# LCDClock.net
KiCad netlist of a schematic drawn in EAGLE
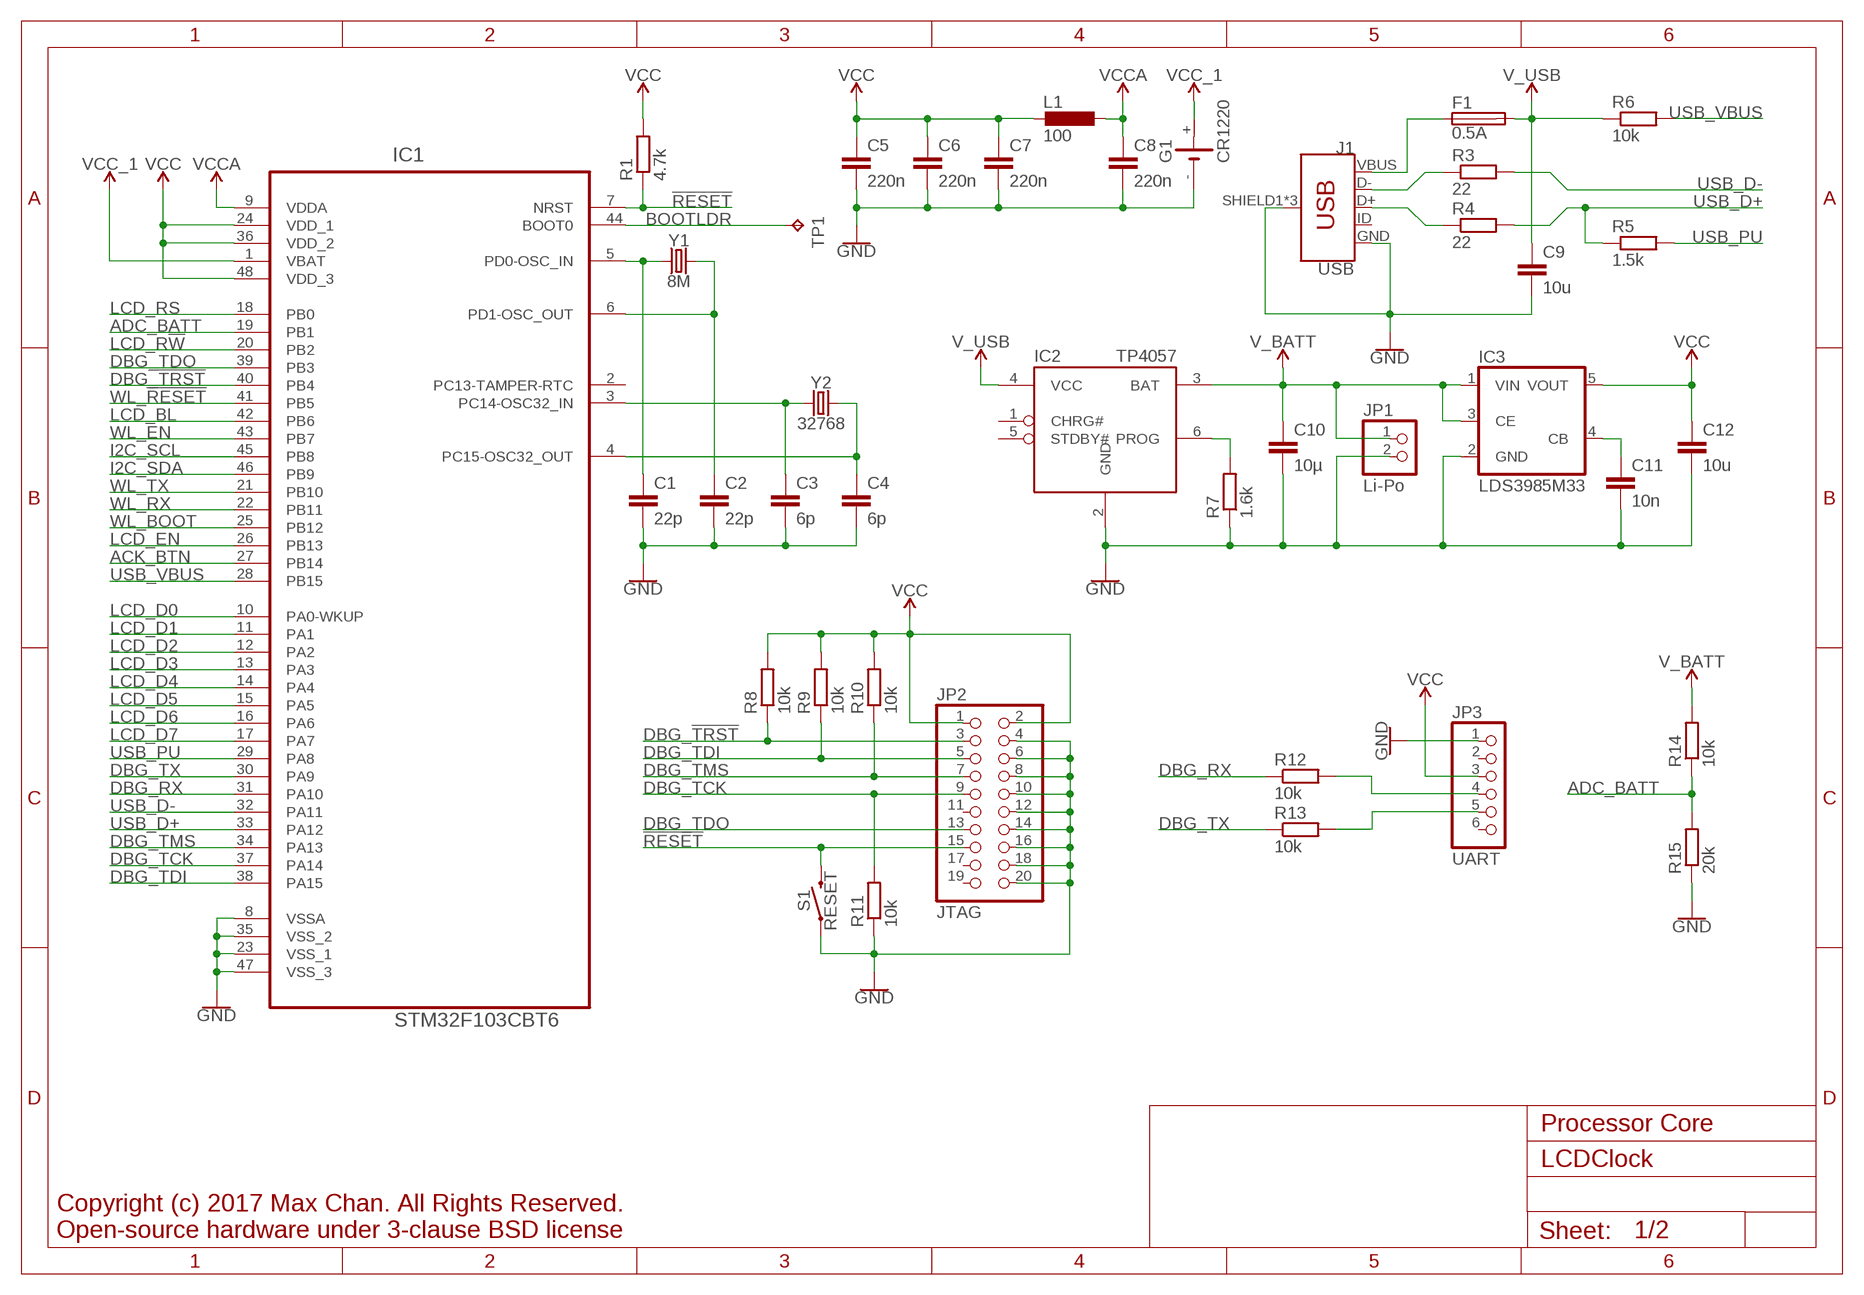
[diagram p0: schematic, sheet 1]
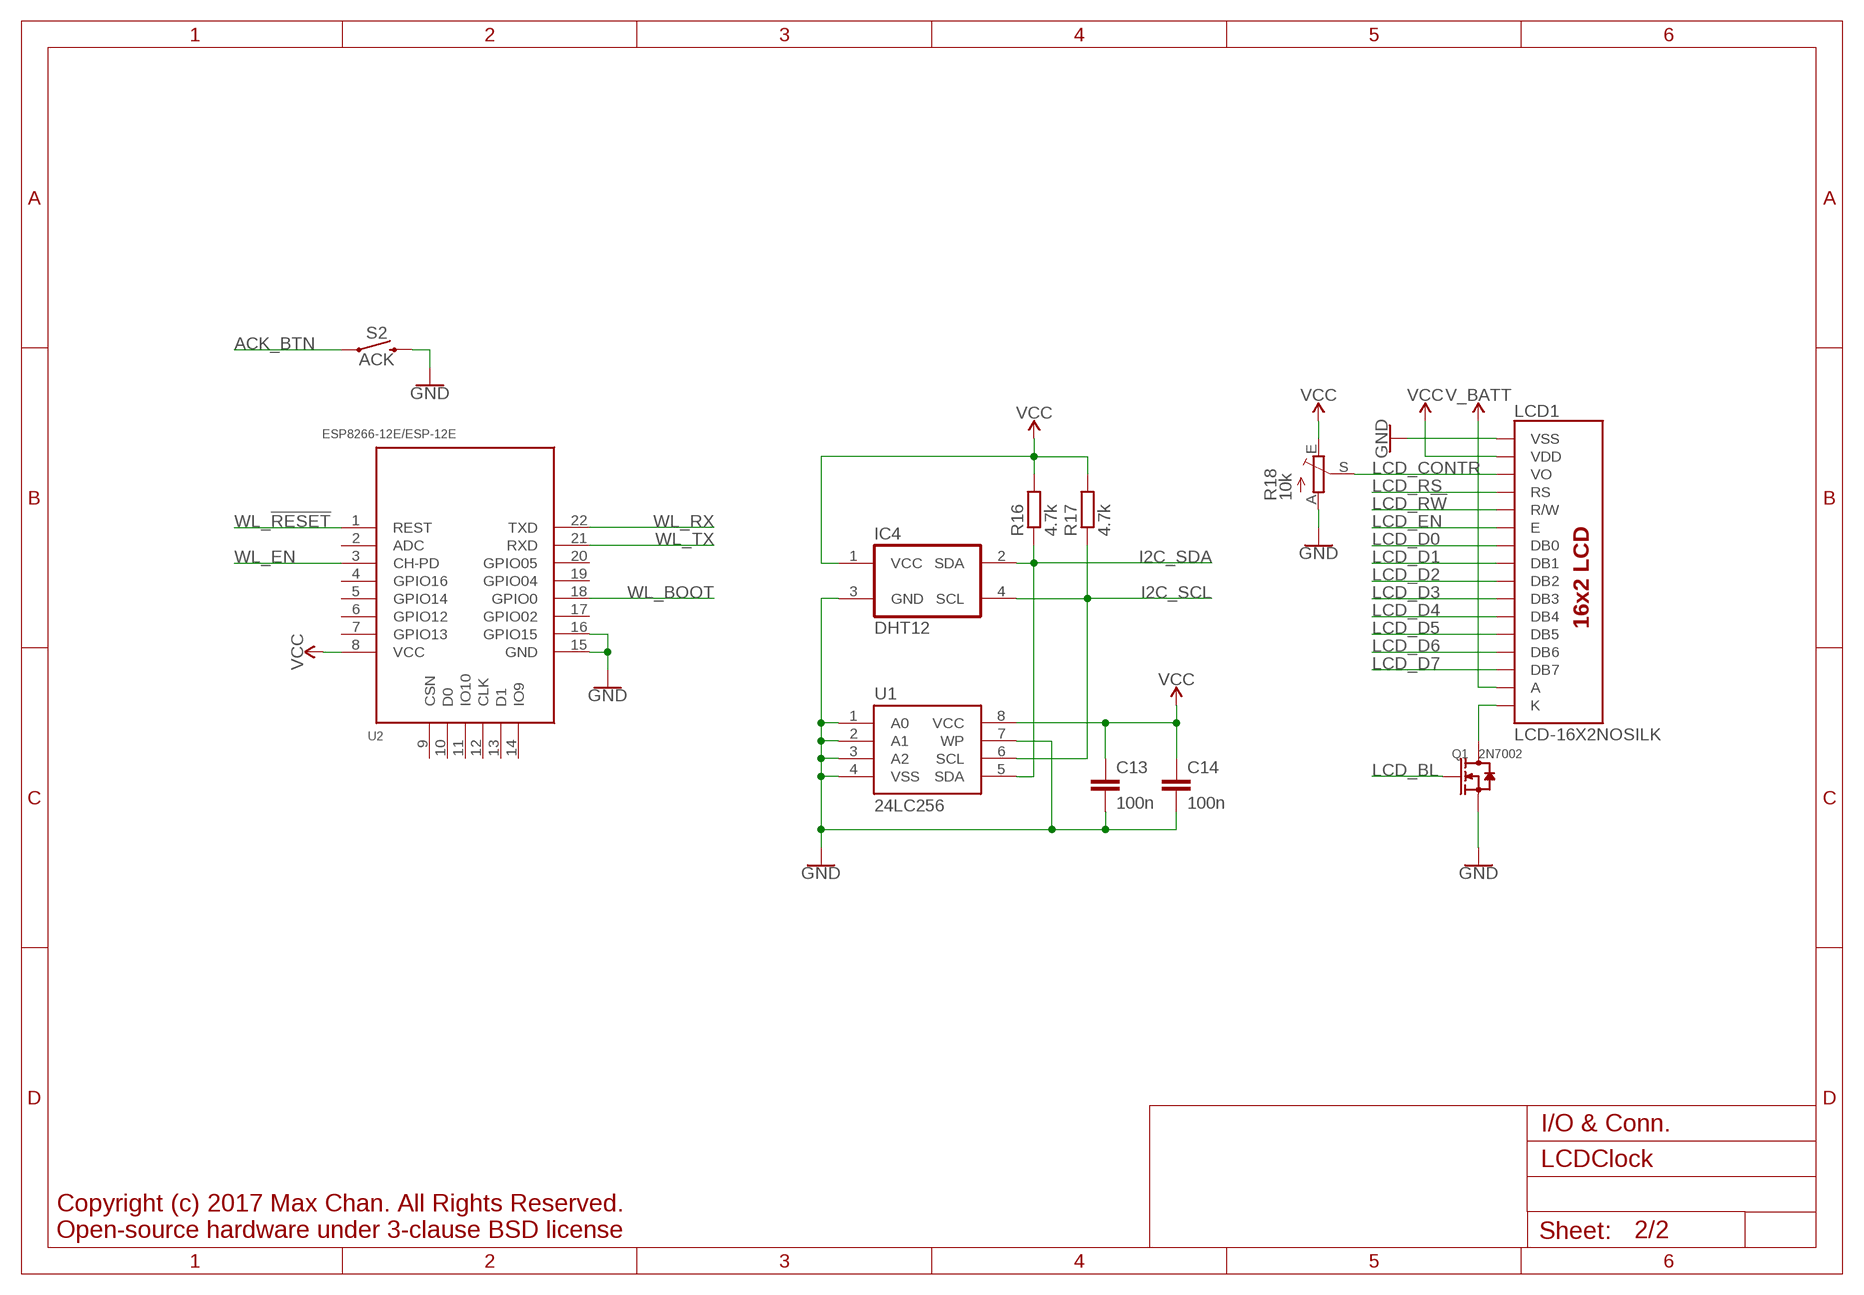
[diagram p1: schematic, sheet 2]

(export (version "E")
  (design (tool "Eeschema 10.0.6"))
  (components
    (comp (ref "C13")
      (value "100n")
      (footprint "eagle-import:C0603")
      (libsource (lib "eagle-import") (part "C-EUC0603"))
    )
    (comp (ref "C14")
      (value "100n")
      (footprint "eagle-import:C0603")
      (libsource (lib "eagle-import") (part "C-EUC0603"))
    )
    (comp (ref "IC4")
      (value "DHT12")
      (footprint "eagle-import:DHT12")
      (libsource (lib "eagle-import") (part "DHT12"))
    )
    (comp (ref "LCD1")
      (value "LCD-16X2NOSILK")
      (footprint "eagle-import:LCD-16X2_NOSILK")
      (libsource (lib "eagle-import") (part "LCD-16X2NOSILK"))
    )
    (comp (ref "Q1")
      (value "2N7002")
      (footprint "eagle-import:SOT-23")
      (fields (field (name "MPN") "2N7002,215"))
      (libsource (lib "eagle-import") (part "SMD-MOSFET-N-CH-60V-300MA-LOGIC-LEVEL-FET-2N7002(SOT-23)"))
    )
    (comp (ref "R16")
      (value "4.7k")
      (footprint "eagle-import:R0603")
      (libsource (lib "eagle-import") (part "R-EU_R0603"))
    )
    (comp (ref "R17")
      (value "4.7k")
      (footprint "eagle-import:R0603")
      (libsource (lib "eagle-import") (part "R-EU_R0603"))
    )
    (comp (ref "R18")
      (value "10k")
      (footprint "eagle-import:CA6V")
      (libsource (lib "eagle-import") (part "TRIM_EU-CA6V"))
    )
    (comp (ref "S2")
      (value "ACK")
      (footprint "eagle-import:TACTILE_SWITCH_PTH_RIGHT_ANGLE_KIT")
      (libsource (lib "eagle-import") (part "MOMENTARY-SWITCH-SPST-PTH-RIGHT-ANGLE-KIT"))
    )
    (comp (ref "U1")
      (value "24LC256")
      (footprint "eagle-import:SO08")
      (libsource (lib "eagle-import") (part "EEPROM-I2CSMD"))
    )
    (comp (ref "U2")
      (value "ESP8266-12E/ESP-12E")
      (footprint "eagle-import:LGA22-2.0-24X16MM")
      (libsource (lib "eagle-import") (part "MOUDLE-WIFI-ESP8266-12E/ESP-12E(22P-24X16MM)"))
    )
    (comp (ref "C1")
      (value "22p")
      (footprint "eagle-import:C0603")
      (libsource (lib "eagle-import") (part "C-EUC0603"))
    )
    (comp (ref "C2")
      (value "22p")
      (footprint "eagle-import:C0603")
      (libsource (lib "eagle-import") (part "C-EUC0603"))
    )
    (comp (ref "C3")
      (value "6p")
      (footprint "eagle-import:C0603")
      (libsource (lib "eagle-import") (part "C-EUC0603"))
    )
    (comp (ref "C4")
      (value "6p")
      (footprint "eagle-import:C0603")
      (libsource (lib "eagle-import") (part "C-EUC0603"))
    )
    (comp (ref "C5")
      (value "220n")
      (footprint "eagle-import:C0603")
      (libsource (lib "eagle-import") (part "C-EUC0603"))
    )
    (comp (ref "C6")
      (value "220n")
      (footprint "eagle-import:C0603")
      (libsource (lib "eagle-import") (part "C-EUC0603"))
    )
    (comp (ref "C7")
      (value "220n")
      (footprint "eagle-import:C0603")
      (libsource (lib "eagle-import") (part "C-EUC0603"))
    )
    (comp (ref "C8")
      (value "220n")
      (footprint "eagle-import:C0603")
      (libsource (lib "eagle-import") (part "C-EUC0603"))
    )
    (comp (ref "C9")
      (value "10u")
      (footprint "eagle-import:C0805")
      (libsource (lib "eagle-import") (part "C-EUC0805"))
    )
    (comp (ref "C10")
      (value "10µ")
      (footprint "eagle-import:C0805")
      (libsource (lib "eagle-import") (part "C-EUC0805"))
    )
    (comp (ref "C11")
      (value "10n")
      (footprint "eagle-import:C0603")
      (libsource (lib "eagle-import") (part "C-EUC0603"))
    )
    (comp (ref "C12")
      (value "10u")
      (footprint "eagle-import:C0805")
      (libsource (lib "eagle-import") (part "C-EUC0805"))
    )
    (comp (ref "F1")
      (value "0.5A")
      (footprint "eagle-import:R1206")
      (libsource (lib "eagle-import") (part "FUSER1206"))
    )
    (comp (ref "G1")
      (value "CR1220")
      (footprint "eagle-import:CH291-1220LF")
      (libsource (lib "eagle-import") (part "CH291-1220LF"))
    )
    (comp (ref "IC1")
      (value "STM32F103CBT6")
      (footprint "eagle-import:QFP50P900X900X160-48N")
      (libsource (lib "eagle-import") (part "STM32F103CBT6"))
    )
    (comp (ref "IC2")
      (value "TP4057")
      (footprint "eagle-import:SOT23-6")
      (libsource (lib "eagle-import") (part "TP4057"))
    )
    (comp (ref "IC3")
      (value "LDS3985M33")
      (footprint "eagle-import:SOT25")
      (libsource (lib "eagle-import") (part "TS520533"))
    )
    (comp (ref "J1")
      (value "USB")
      (footprint "eagle-import:USB-B-MICRO-SMD")
      (libsource (lib "eagle-import") (part "USB_MICRO-B_FEMALE-SMT"))
    )
    (comp (ref "JP1")
      (value "Li-Po")
      (footprint "eagle-import:1X02")
      (libsource (lib "eagle-import") (part "PINHD-1X2"))
    )
    (comp (ref "JP2")
      (value "JTAG")
      (footprint "eagle-import:2X10_90")
      (libsource (lib "eagle-import") (part "PINHD-2X10/90"))
    )
    (comp (ref "JP3")
      (value "UART")
      (footprint "eagle-import:1X06_90")
      (libsource (lib "eagle-import") (part "PINHD-1X6/90"))
    )
    (comp (ref "L1")
      (value "100")
      (footprint "eagle-import:L2012C")
      (libsource (lib "eagle-import") (part "L-EUL2012C"))
    )
    (comp (ref "R1")
      (value "4.7k")
      (footprint "eagle-import:R0603")
      (libsource (lib "eagle-import") (part "R-EU_R0603"))
    )
    (comp (ref "R3")
      (value "22")
      (footprint "eagle-import:R0603")
      (libsource (lib "eagle-import") (part "R-EU_R0603"))
    )
    (comp (ref "R4")
      (value "22")
      (footprint "eagle-import:R0603")
      (libsource (lib "eagle-import") (part "R-EU_R0603"))
    )
    (comp (ref "R5")
      (value "1.5k")
      (footprint "eagle-import:R0603")
      (libsource (lib "eagle-import") (part "R-EU_R0603"))
    )
    (comp (ref "R6")
      (value "10k")
      (footprint "eagle-import:R0603")
      (libsource (lib "eagle-import") (part "R-EU_R0603"))
    )
    (comp (ref "R7")
      (value "1.6k")
      (footprint "eagle-import:R0603")
      (libsource (lib "eagle-import") (part "R-EU_R0603"))
    )
    (comp (ref "R8")
      (value "10k")
      (footprint "eagle-import:R0603")
      (libsource (lib "eagle-import") (part "R-EU_R0603"))
    )
    (comp (ref "R9")
      (value "10k")
      (footprint "eagle-import:R0603")
      (libsource (lib "eagle-import") (part "R-EU_R0603"))
    )
    (comp (ref "R10")
      (value "10k")
      (footprint "eagle-import:R0603")
      (libsource (lib "eagle-import") (part "R-EU_R0603"))
    )
    (comp (ref "R11")
      (value "10k")
      (footprint "eagle-import:R0603")
      (libsource (lib "eagle-import") (part "R-EU_R0603"))
    )
    (comp (ref "R12")
      (value "10k")
      (footprint "eagle-import:R0603")
      (libsource (lib "eagle-import") (part "R-EU_R0603"))
    )
    (comp (ref "R13")
      (value "10k")
      (footprint "eagle-import:R0603")
      (libsource (lib "eagle-import") (part "R-EU_R0603"))
    )
    (comp (ref "R14")
      (value "10k")
      (footprint "eagle-import:R0603")
      (libsource (lib "eagle-import") (part "R-EU_R0603"))
    )
    (comp (ref "R15")
      (value "20k")
      (footprint "eagle-import:R0603")
      (libsource (lib "eagle-import") (part "R-EU_R0603"))
    )
    (comp (ref "S1")
      (value "RESET")
      (footprint "eagle-import:TACTILE_SWITCH_SMD_6.0X3.5MM")
      (libsource (lib "eagle-import") (part "MOMENTARY-SWITCH-SPST-SMD-6.0X3.5MM"))
    )
    (comp (ref "TP1")
      (value "TPTP10R")
      (footprint "eagle-import:TP10R")
      (libsource (lib "eagle-import") (part "TPTP10R"))
    )
    (comp (ref "Y1")
      (value "8M")
      (footprint "eagle-import:CRYSTAL-SMD-5X3.2-4PAD")
      (libsource (lib "eagle-import") (part "CRYSTALSMD-5X3.2-4PAD"))
    )
    (comp (ref "Y2")
      (value "32768")
      (footprint "eagle-import:CRYSTAL-SMD-3.2X1.5MM")
      (libsource (lib "eagle-import") (part "CRYSTALSMD-3.2X1.5"))
    )
  )
  (nets
    (net (code "1") (name "ACK_BTN") (class "Default")
      (node (ref "IC1") (pin "27") (pinfunction "PB14_27") (pintype "bidirectional"))
      (node (ref "S2") (pin "1") (pinfunction "1_1") (pintype "passive"))
    )
    (net (code "2") (name "ADC_BATT") (class "Default")
      (node (ref "IC1") (pin "19") (pinfunction "PB1_19") (pintype "bidirectional"))
      (node (ref "R14") (pin "1") (pinfunction "1_1") (pintype "passive"))
      (node (ref "R15") (pin "2") (pinfunction "2_2") (pintype "passive"))
    )
    (net (code "3") (name "BOOTLDR") (class "Default")
      (node (ref "IC1") (pin "44") (pinfunction "BOOT0_44") (pintype "bidirectional"))
      (node (ref "TP1") (pin "TP") (pinfunction "TP_TP") (pintype "input"))
    )
    (net (code "4") (name "DBG_RX") (class "Default")
      (node (ref "IC1") (pin "31") (pinfunction "PA10_31") (pintype "bidirectional"))
      (node (ref "R12") (pin "1") (pinfunction "1_1") (pintype "passive"))
    )
    (net (code "5") (name "DBG_TCK") (class "Default")
      (node (ref "IC1") (pin "37") (pinfunction "PA14_37") (pintype "bidirectional"))
      (node (ref "JP2") (pin "9") (pinfunction "9_9") (pintype "passive"))
      (node (ref "R11") (pin "2") (pinfunction "2_2") (pintype "passive"))
    )
    (net (code "6") (name "DBG_TDI") (class "Default")
      (node (ref "IC1") (pin "38") (pinfunction "PA15_38") (pintype "bidirectional"))
      (node (ref "JP2") (pin "5") (pinfunction "5_5") (pintype "passive"))
      (node (ref "R9") (pin "1") (pinfunction "1_1") (pintype "passive"))
    )
    (net (code "7") (name "DBG_TDO") (class "Default")
      (node (ref "IC1") (pin "39") (pinfunction "PB3_39") (pintype "bidirectional"))
      (node (ref "JP2") (pin "13") (pinfunction "13_13") (pintype "passive"))
    )
    (net (code "8") (name "DBG_TMS") (class "Default")
      (node (ref "IC1") (pin "34") (pinfunction "PA13_34") (pintype "bidirectional"))
      (node (ref "JP2") (pin "7") (pinfunction "7_7") (pintype "passive"))
      (node (ref "R10") (pin "1") (pinfunction "1_1") (pintype "passive"))
    )
    (net (code "9") (name "DBG_TX") (class "Default")
      (node (ref "IC1") (pin "30") (pinfunction "PA9_30") (pintype "bidirectional"))
      (node (ref "R13") (pin "1") (pinfunction "1_1") (pintype "passive"))
    )
    (net (code "10") (name "DBG_~{TRST}") (class "Default")
      (node (ref "IC1") (pin "40") (pinfunction "PB4_40") (pintype "bidirectional"))
      (node (ref "JP2") (pin "3") (pinfunction "3_3") (pintype "passive"))
      (node (ref "R8") (pin "1") (pinfunction "1_1") (pintype "passive"))
    )
    (net (code "11") (name "GND") (class "Default")
      (node (ref "C1") (pin "2") (pinfunction "2_2") (pintype "passive"))
      (node (ref "C10") (pin "2") (pinfunction "2_2") (pintype "passive"))
      (node (ref "C11") (pin "2") (pinfunction "2_2") (pintype "passive"))
      (node (ref "C12") (pin "2") (pinfunction "2_2") (pintype "passive"))
      (node (ref "C13") (pin "2") (pinfunction "2_2") (pintype "passive"))
      (node (ref "C14") (pin "2") (pinfunction "2_2") (pintype "passive"))
      (node (ref "C2") (pin "2") (pinfunction "2_2") (pintype "passive"))
      (node (ref "C3") (pin "2") (pinfunction "2_2") (pintype "passive"))
      (node (ref "C4") (pin "2") (pinfunction "2_2") (pintype "passive"))
      (node (ref "C5") (pin "2") (pinfunction "2_2") (pintype "passive"))
      (node (ref "C6") (pin "2") (pinfunction "2_2") (pintype "passive"))
      (node (ref "C7") (pin "2") (pinfunction "2_2") (pintype "passive"))
      (node (ref "C8") (pin "2") (pinfunction "2_2") (pintype "passive"))
      (node (ref "C9") (pin "2") (pinfunction "2_2") (pintype "passive"))
      (node (ref "G1") (pin "-") (pinfunction "-_-") (pintype "passive"))
      (node (ref "IC1") (pin "23") (pinfunction "VSS_1_23") (pintype "bidirectional"))
      (node (ref "IC1") (pin "35") (pinfunction "VSS_2_35") (pintype "passive"))
      (node (ref "IC1") (pin "47") (pinfunction "VSS_3_47") (pintype "passive"))
      (node (ref "IC1") (pin "8") (pinfunction "VSSA_8") (pintype "passive"))
      (node (ref "IC2") (pin "2") (pinfunction "GND_2") (pintype "power_in"))
      (node (ref "IC3") (pin "2") (pinfunction "GND_2") (pintype "passive"))
      (node (ref "IC4") (pin "3") (pinfunction "GND_3") (pintype "power_in"))
      (node (ref "J1") (pin "GND") (pinfunction "GND_GND") (pintype "power_in"))
      (node (ref "J1") (pin "SHIELD1") (pinfunction "SHIELD_SHIELD1") (pintype "bidirectional"))
      (node (ref "J1") (pin "SHIELD2") (pinfunction "SHIELD_SHIELD2") (pintype "bidirectional"))
      (node (ref "J1") (pin "SHIELD3") (pinfunction "SHIELD_SHIELD3") (pintype "bidirectional"))
      (node (ref "JP1") (pin "2") (pinfunction "2_2") (pintype "passive"))
      (node (ref "JP2") (pin "10") (pinfunction "10_10") (pintype "passive"))
      (node (ref "JP2") (pin "12") (pinfunction "12_12") (pintype "passive"))
      (node (ref "JP2") (pin "14") (pinfunction "14_14") (pintype "passive"))
      (node (ref "JP2") (pin "16") (pinfunction "16_16") (pintype "passive"))
      (node (ref "JP2") (pin "18") (pinfunction "18_18") (pintype "passive"))
      (node (ref "JP2") (pin "20") (pinfunction "20_20") (pintype "passive"))
      (node (ref "JP2") (pin "4") (pinfunction "4_4") (pintype "passive"))
      (node (ref "JP2") (pin "6") (pinfunction "6_6") (pintype "passive"))
      (node (ref "JP2") (pin "8") (pinfunction "8_8") (pintype "passive"))
      (node (ref "JP3") (pin "1") (pinfunction "1_1") (pintype "passive"))
      (node (ref "LCD1") (pin "1") (pinfunction "VSS_1") (pintype "power_in"))
      (node (ref "Q1") (pin "2") (pinfunction "S_2") (pintype "passive"))
      (node (ref "R11") (pin "1") (pinfunction "1_1") (pintype "passive"))
      (node (ref "R15") (pin "1") (pinfunction "1_1") (pintype "passive"))
      (node (ref "R18") (pin "A") (pinfunction "A_A") (pintype "passive"))
      (node (ref "R7") (pin "1") (pinfunction "1_1") (pintype "passive"))
      (node (ref "S1") (pin "1") (pinfunction "1_1") (pintype "passive"))
      (node (ref "S2") (pin "2") (pinfunction "2_2") (pintype "passive"))
      (node (ref "U1") (pin "1") (pinfunction "A0_1") (pintype "bidirectional"))
      (node (ref "U1") (pin "2") (pinfunction "A1_2") (pintype "bidirectional"))
      (node (ref "U1") (pin "3") (pinfunction "A2_3") (pintype "bidirectional"))
      (node (ref "U1") (pin "4") (pinfunction "VSS_4") (pintype "power_in"))
      (node (ref "U1") (pin "7") (pinfunction "WP_7") (pintype "bidirectional"))
      (node (ref "U2") (pin "15") (pinfunction "GND_15") (pintype "bidirectional"))
      (node (ref "U2") (pin "16") (pinfunction "GPIO15_16") (pintype "bidirectional"))
    )
    (net (code "12") (name "I2C_SCL") (class "Default")
      (node (ref "IC1") (pin "45") (pinfunction "PB8_45") (pintype "bidirectional"))
      (node (ref "IC4") (pin "4") (pinfunction "SCL_4") (pintype "power_in"))
      (node (ref "R17") (pin "1") (pinfunction "1_1") (pintype "passive"))
      (node (ref "U1") (pin "6") (pinfunction "SCL_6") (pintype "bidirectional"))
    )
    (net (code "13") (name "I2C_SDA") (class "Default")
      (node (ref "IC1") (pin "46") (pinfunction "PB9_46") (pintype "bidirectional"))
      (node (ref "IC4") (pin "2") (pinfunction "SDA_2") (pintype "open_collector"))
      (node (ref "R16") (pin "1") (pinfunction "1_1") (pintype "passive"))
      (node (ref "U1") (pin "5") (pinfunction "SDA_5") (pintype "bidirectional"))
    )
    (net (code "14") (name "LCD_BL") (class "Default")
      (node (ref "IC1") (pin "42") (pinfunction "PB6_42") (pintype "bidirectional"))
      (node (ref "Q1") (pin "1") (pinfunction "G_1") (pintype "passive"))
    )
    (net (code "15") (name "LCD_CONTR") (class "Default")
      (node (ref "LCD1") (pin "3") (pinfunction "VO_3") (pintype "bidirectional"))
      (node (ref "R18") (pin "S") (pinfunction "S_S") (pintype "passive"))
    )
    (net (code "16") (name "LCD_D0") (class "Default")
      (node (ref "IC1") (pin "10") (pinfunction "PA0-WKUP_10") (pintype "bidirectional"))
      (node (ref "LCD1") (pin "7") (pinfunction "DB0_7") (pintype "bidirectional"))
    )
    (net (code "17") (name "LCD_D1") (class "Default")
      (node (ref "IC1") (pin "11") (pinfunction "PA1_11") (pintype "bidirectional"))
      (node (ref "LCD1") (pin "8") (pinfunction "DB1_8") (pintype "bidirectional"))
    )
    (net (code "18") (name "LCD_D2") (class "Default")
      (node (ref "IC1") (pin "12") (pinfunction "PA2_12") (pintype "bidirectional"))
      (node (ref "LCD1") (pin "9") (pinfunction "DB2_9") (pintype "bidirectional"))
    )
    (net (code "19") (name "LCD_D3") (class "Default")
      (node (ref "IC1") (pin "13") (pinfunction "PA3_13") (pintype "bidirectional"))
      (node (ref "LCD1") (pin "10") (pinfunction "DB3_10") (pintype "bidirectional"))
    )
    (net (code "20") (name "LCD_D4") (class "Default")
      (node (ref "IC1") (pin "14") (pinfunction "PA4_14") (pintype "bidirectional"))
      (node (ref "LCD1") (pin "11") (pinfunction "DB4_11") (pintype "bidirectional"))
    )
    (net (code "21") (name "LCD_D5") (class "Default")
      (node (ref "IC1") (pin "15") (pinfunction "PA5_15") (pintype "bidirectional"))
      (node (ref "LCD1") (pin "12") (pinfunction "DB5_12") (pintype "bidirectional"))
    )
    (net (code "22") (name "LCD_D6") (class "Default")
      (node (ref "IC1") (pin "16") (pinfunction "PA6_16") (pintype "bidirectional"))
      (node (ref "LCD1") (pin "13") (pinfunction "DB6_13") (pintype "bidirectional"))
    )
    (net (code "23") (name "LCD_D7") (class "Default")
      (node (ref "IC1") (pin "17") (pinfunction "PA7_17") (pintype "bidirectional"))
      (node (ref "LCD1") (pin "14") (pinfunction "DB7_14") (pintype "bidirectional"))
    )
    (net (code "24") (name "LCD_EN") (class "Default")
      (node (ref "IC1") (pin "26") (pinfunction "PB13_26") (pintype "bidirectional"))
      (node (ref "LCD1") (pin "6") (pinfunction "E_6") (pintype "input"))
    )
    (net (code "25") (name "LCD_RS") (class "Default")
      (node (ref "IC1") (pin "18") (pinfunction "PB0_18") (pintype "bidirectional"))
      (node (ref "LCD1") (pin "4") (pinfunction "RS_4") (pintype "input"))
    )
    (net (code "26") (name "LCD_R~{W}") (class "Default")
      (node (ref "IC1") (pin "20") (pinfunction "PB2_20") (pintype "bidirectional"))
      (node (ref "LCD1") (pin "5") (pinfunction "R/W_5") (pintype "input"))
    )
    (net (code "27") (name "Net-(F1-Pad1)") (class "Default")
      (node (ref "F1") (pin "1") (pinfunction "1_1") (pintype "passive"))
      (node (ref "J1") (pin "VBUS") (pinfunction "VBUS_VBUS") (pintype "power_in"))
    )
    (net (code "28") (name "Net-(IC1-PC14-OSC32_IN)") (class "Default")
      (node (ref "C3") (pin "1") (pinfunction "1_1") (pintype "passive"))
      (node (ref "IC1") (pin "3") (pinfunction "PC14-OSC32_IN_3") (pintype "bidirectional"))
      (node (ref "Y2") (pin "P$1") (pinfunction "1_P$1") (pintype "passive"))
    )
    (net (code "29") (name "Net-(IC1-PC15-OSC32_OUT)") (class "Default")
      (node (ref "C4") (pin "1") (pinfunction "1_1") (pintype "passive"))
      (node (ref "IC1") (pin "4") (pinfunction "PC15-OSC32_OUT_4") (pintype "bidirectional"))
      (node (ref "Y2") (pin "P$2") (pinfunction "2_P$2") (pintype "passive"))
    )
    (net (code "30") (name "Net-(IC1-PD0-OSC_IN)") (class "Default")
      (node (ref "C1") (pin "1") (pinfunction "1_1") (pintype "passive"))
      (node (ref "IC1") (pin "5") (pinfunction "PD0-OSC_IN_5") (pintype "bidirectional"))
      (node (ref "Y1") (pin "1") (pinfunction "1_1") (pintype "passive"))
    )
    (net (code "31") (name "Net-(IC1-PD1-OSC_OUT)") (class "Default")
      (node (ref "C2") (pin "1") (pinfunction "1_1") (pintype "passive"))
      (node (ref "IC1") (pin "6") (pinfunction "PD1-OSC_OUT_6") (pintype "bidirectional"))
      (node (ref "Y1") (pin "3") (pinfunction "2_3") (pintype "passive"))
    )
    (net (code "32") (name "Net-(IC2-PROG)") (class "Default")
      (node (ref "IC2") (pin "6") (pinfunction "PROG_6") (pintype "input"))
      (node (ref "R7") (pin "2") (pinfunction "2_2") (pintype "passive"))
    )
    (net (code "33") (name "Net-(IC3-CB)") (class "Default")
      (node (ref "C11") (pin "1") (pinfunction "1_1") (pintype "passive"))
      (node (ref "IC3") (pin "4") (pinfunction "CB_4") (pintype "input"))
    )
    (net (code "34") (name "Net-(J1-PadD+)") (class "Default")
      (node (ref "J1") (pin "D+") (pinfunction "D+_D+") (pintype "bidirectional"))
      (node (ref "R4") (pin "1") (pinfunction "1_1") (pintype "passive"))
    )
    (net (code "35") (name "Net-(J1-PadD-)") (class "Default")
      (node (ref "J1") (pin "D-") (pinfunction "D-_D-") (pintype "bidirectional"))
      (node (ref "R3") (pin "1") (pinfunction "1_1") (pintype "passive"))
    )
    (net (code "36") (name "Net-(JP3-Pad4)") (class "Default")
      (node (ref "JP3") (pin "4") (pinfunction "4_4") (pintype "passive"))
      (node (ref "R12") (pin "2") (pinfunction "2_2") (pintype "passive"))
    )
    (net (code "37") (name "Net-(JP3-Pad5)") (class "Default")
      (node (ref "JP3") (pin "5") (pinfunction "5_5") (pintype "passive"))
      (node (ref "R13") (pin "2") (pinfunction "2_2") (pintype "passive"))
    )
    (net (code "38") (name "Net-(LCD1-K)") (class "Default")
      (node (ref "LCD1") (pin "16") (pinfunction "K_16") (pintype "power_in"))
      (node (ref "Q1") (pin "3") (pinfunction "D_3") (pintype "passive"))
    )
    (net (code "39") (name "USB_D+") (class "Default")
      (node (ref "IC1") (pin "33") (pinfunction "PA12_33") (pintype "bidirectional"))
      (node (ref "R4") (pin "2") (pinfunction "2_2") (pintype "passive"))
      (node (ref "R5") (pin "1") (pinfunction "1_1") (pintype "passive"))
    )
    (net (code "40") (name "USB_D-") (class "Default")
      (node (ref "IC1") (pin "32") (pinfunction "PA11_32") (pintype "power_in"))
      (node (ref "R3") (pin "2") (pinfunction "2_2") (pintype "passive"))
    )
    (net (code "41") (name "USB_PU") (class "Default")
      (node (ref "IC1") (pin "29") (pinfunction "PA8_29") (pintype "bidirectional"))
      (node (ref "R5") (pin "2") (pinfunction "2_2") (pintype "passive"))
    )
    (net (code "42") (name "USB_VBUS") (class "Default")
      (node (ref "IC1") (pin "28") (pinfunction "PB15_28") (pintype "bidirectional"))
      (node (ref "R6") (pin "2") (pinfunction "2_2") (pintype "passive"))
    )
    (net (code "43") (name "VCC") (class "Default")
      (node (ref "C12") (pin "1") (pinfunction "1_1") (pintype "passive"))
      (node (ref "C13") (pin "1") (pinfunction "1_1") (pintype "passive"))
      (node (ref "C14") (pin "1") (pinfunction "1_1") (pintype "passive"))
      (node (ref "C5") (pin "1") (pinfunction "1_1") (pintype "passive"))
      (node (ref "C6") (pin "1") (pinfunction "1_1") (pintype "passive"))
      (node (ref "C7") (pin "1") (pinfunction "1_1") (pintype "passive"))
      (node (ref "IC1") (pin "24") (pinfunction "VDD_1_24") (pintype "bidirectional"))
      (node (ref "IC1") (pin "36") (pinfunction "VDD_2_36") (pintype "power_in"))
      (node (ref "IC1") (pin "48") (pinfunction "VDD_3_48") (pintype "power_in"))
      (node (ref "IC3") (pin "5") (pinfunction "VOUT_5") (pintype "passive"))
      (node (ref "IC4") (pin "1") (pinfunction "VCC_1") (pintype "power_in"))
      (node (ref "JP2") (pin "1") (pinfunction "1_1") (pintype "passive"))
      (node (ref "JP2") (pin "2") (pinfunction "2_2") (pintype "passive"))
      (node (ref "JP3") (pin "3") (pinfunction "3_3") (pintype "passive"))
      (node (ref "L1") (pin "2") (pinfunction "2_2") (pintype "passive"))
      (node (ref "LCD1") (pin "2") (pinfunction "VDD_2") (pintype "power_in"))
      (node (ref "R1") (pin "2") (pinfunction "2_2") (pintype "passive"))
      (node (ref "R10") (pin "2") (pinfunction "2_2") (pintype "passive"))
      (node (ref "R16") (pin "2") (pinfunction "2_2") (pintype "passive"))
      (node (ref "R17") (pin "2") (pinfunction "2_2") (pintype "passive"))
      (node (ref "R18") (pin "E") (pinfunction "E_E") (pintype "passive"))
      (node (ref "R8") (pin "2") (pinfunction "2_2") (pintype "passive"))
      (node (ref "R9") (pin "2") (pinfunction "2_2") (pintype "passive"))
      (node (ref "U1") (pin "8") (pinfunction "VCC_8") (pintype "power_in"))
      (node (ref "U2") (pin "8") (pinfunction "VCC_8") (pintype "bidirectional"))
    )
    (net (code "44") (name "VCCA") (class "Default")
      (node (ref "C8") (pin "1") (pinfunction "1_1") (pintype "passive"))
      (node (ref "IC1") (pin "9") (pinfunction "VDDA_9") (pintype "power_in"))
      (node (ref "L1") (pin "1") (pinfunction "1_1") (pintype "passive"))
    )
    (net (code "45") (name "VCC_1") (class "Default")
      (node (ref "G1") (pin "+") (pinfunction "+_+") (pintype "passive"))
      (node (ref "IC1") (pin "1") (pinfunction "VBAT_1") (pintype "input"))
    )
    (net (code "46") (name "V_BATT") (class "Default")
      (node (ref "C10") (pin "1") (pinfunction "1_1") (pintype "passive"))
      (node (ref "IC2") (pin "3") (pinfunction "BAT_3") (pintype "output"))
      (node (ref "IC3") (pin "1") (pinfunction "VIN_1") (pintype "input"))
      (node (ref "IC3") (pin "3") (pinfunction "CE_3") (pintype "input"))
      (node (ref "JP1") (pin "1") (pinfunction "1_1") (pintype "passive"))
      (node (ref "LCD1") (pin "15") (pinfunction "A_15") (pintype "power_in"))
      (node (ref "R14") (pin "2") (pinfunction "2_2") (pintype "passive"))
    )
    (net (code "47") (name "V_USB") (class "Default")
      (node (ref "C9") (pin "1") (pinfunction "1_1") (pintype "passive"))
      (node (ref "F1") (pin "2") (pinfunction "2_2") (pintype "passive"))
      (node (ref "IC2") (pin "4") (pinfunction "VCC_4") (pintype "bidirectional"))
      (node (ref "R6") (pin "1") (pinfunction "1_1") (pintype "passive"))
    )
    (net (code "48") (name "WL_BOOT") (class "Default")
      (node (ref "IC1") (pin "25") (pinfunction "PB12_25") (pintype "bidirectional"))
      (node (ref "U2") (pin "18") (pinfunction "GPIO0_18") (pintype "bidirectional"))
    )
    (net (code "49") (name "WL_EN") (class "Default")
      (node (ref "IC1") (pin "43") (pinfunction "PB7_43") (pintype "bidirectional"))
      (node (ref "U2") (pin "3") (pinfunction "CH-PD_3") (pintype "bidirectional"))
    )
    (net (code "50") (name "WL_RX") (class "Default")
      (node (ref "IC1") (pin "22") (pinfunction "PB11_22") (pintype "bidirectional"))
      (node (ref "U2") (pin "22") (pinfunction "TXD_22") (pintype "bidirectional"))
    )
    (net (code "51") (name "WL_TX") (class "Default")
      (node (ref "IC1") (pin "21") (pinfunction "PB10_21") (pintype "bidirectional"))
      (node (ref "U2") (pin "21") (pinfunction "RXD_21") (pintype "bidirectional"))
    )
    (net (code "52") (name "WL_~{RESET}") (class "Default")
      (node (ref "IC1") (pin "41") (pinfunction "PB5_41") (pintype "bidirectional"))
      (node (ref "U2") (pin "1") (pinfunction "REST_1") (pintype "bidirectional"))
    )
    (net (code "53") (name "unconnected-(IC1-PC13-TAMPER-RTC-Pad2)") (class "Default")
      (node (ref "IC1") (pin "2") (pinfunction "PC13-TAMPER-RTC_2") (pintype "bidirectional"))
    )
    (net (code "54") (name "unconnected-(IC2-CHRG#-Pad1)") (class "Default")
      (node (ref "IC2") (pin "1") (pinfunction "CHRG#_1") (pintype "output"))
    )
    (net (code "55") (name "unconnected-(IC2-STDBY#-Pad5)") (class "Default")
      (node (ref "IC2") (pin "5") (pinfunction "STDBY#_5") (pintype "output"))
    )
    (net (code "56") (name "unconnected-(J1-PadID)") (class "Default")
      (node (ref "J1") (pin "ID") (pinfunction "ID_ID") (pintype "bidirectional"))
    )
    (net (code "57") (name "unconnected-(JP2-Pad11)") (class "Default")
      (node (ref "JP2") (pin "11") (pinfunction "11_11") (pintype "passive"))
    )
    (net (code "58") (name "unconnected-(JP2-Pad17)") (class "Default")
      (node (ref "JP2") (pin "17") (pinfunction "17_17") (pintype "passive"))
    )
    (net (code "59") (name "unconnected-(JP2-Pad19)") (class "Default")
      (node (ref "JP2") (pin "19") (pinfunction "19_19") (pintype "passive"))
    )
    (net (code "60") (name "unconnected-(JP3-Pad2)") (class "Default")
      (node (ref "JP3") (pin "2") (pinfunction "2_2") (pintype "passive"))
    )
    (net (code "61") (name "unconnected-(JP3-Pad6)") (class "Default")
      (node (ref "JP3") (pin "6") (pinfunction "6_6") (pintype "passive"))
    )
    (net (code "62") (name "unconnected-(U2-ADC-Pad2)") (class "Default")
      (node (ref "U2") (pin "2") (pinfunction "ADC_2") (pintype "bidirectional"))
    )
    (net (code "63") (name "unconnected-(U2-CLK-Pad12)") (class "Default")
      (node (ref "U2") (pin "12") (pinfunction "CLK_12") (pintype "bidirectional"))
    )
    (net (code "64") (name "unconnected-(U2-CSN-Pad9)") (class "Default")
      (node (ref "U2") (pin "9") (pinfunction "CSN_9") (pintype "bidirectional"))
    )
    (net (code "65") (name "unconnected-(U2-D0-Pad10)") (class "Default")
      (node (ref "U2") (pin "10") (pinfunction "D0_10") (pintype "bidirectional"))
    )
    (net (code "66") (name "unconnected-(U2-D1-Pad13)") (class "Default")
      (node (ref "U2") (pin "13") (pinfunction "D1_13") (pintype "bidirectional"))
    )
    (net (code "67") (name "unconnected-(U2-GPIO02-Pad17)") (class "Default")
      (node (ref "U2") (pin "17") (pinfunction "GPIO02_17") (pintype "bidirectional"))
    )
    (net (code "68") (name "unconnected-(U2-GPIO04-Pad19)") (class "Default")
      (node (ref "U2") (pin "19") (pinfunction "GPIO04_19") (pintype "bidirectional"))
    )
    (net (code "69") (name "unconnected-(U2-GPIO05-Pad20)") (class "Default")
      (node (ref "U2") (pin "20") (pinfunction "GPIO05_20") (pintype "bidirectional"))
    )
    (net (code "70") (name "unconnected-(U2-GPIO12-Pad6)") (class "Default")
      (node (ref "U2") (pin "6") (pinfunction "GPIO12_6") (pintype "bidirectional"))
    )
    (net (code "71") (name "unconnected-(U2-GPIO13-Pad7)") (class "Default")
      (node (ref "U2") (pin "7") (pinfunction "GPIO13_7") (pintype "bidirectional"))
    )
    (net (code "72") (name "unconnected-(U2-GPIO14-Pad5)") (class "Default")
      (node (ref "U2") (pin "5") (pinfunction "GPIO14_5") (pintype "bidirectional"))
    )
    (net (code "73") (name "unconnected-(U2-GPIO16-Pad4)") (class "Default")
      (node (ref "U2") (pin "4") (pinfunction "GPIO16_4") (pintype "bidirectional"))
    )
    (net (code "74") (name "unconnected-(U2-IO9-Pad14)") (class "Default")
      (node (ref "U2") (pin "14") (pinfunction "IO9_14") (pintype "bidirectional"))
    )
    (net (code "75") (name "unconnected-(U2-IO10-Pad11)") (class "Default")
      (node (ref "U2") (pin "11") (pinfunction "IO10_11") (pintype "bidirectional"))
    )
    (net (code "76") (name "~{RESET}") (class "Default")
      (node (ref "IC1") (pin "7") (pinfunction "NRST_7") (pintype "bidirectional"))
      (node (ref "JP2") (pin "15") (pinfunction "15_15") (pintype "passive"))
      (node (ref "R1") (pin "1") (pinfunction "1_1") (pintype "passive"))
      (node (ref "S1") (pin "2") (pinfunction "2_2") (pintype "passive"))
    )
  )
)
